# Blank.net
KiCad netlist of a schematic drawn in Altium Designer
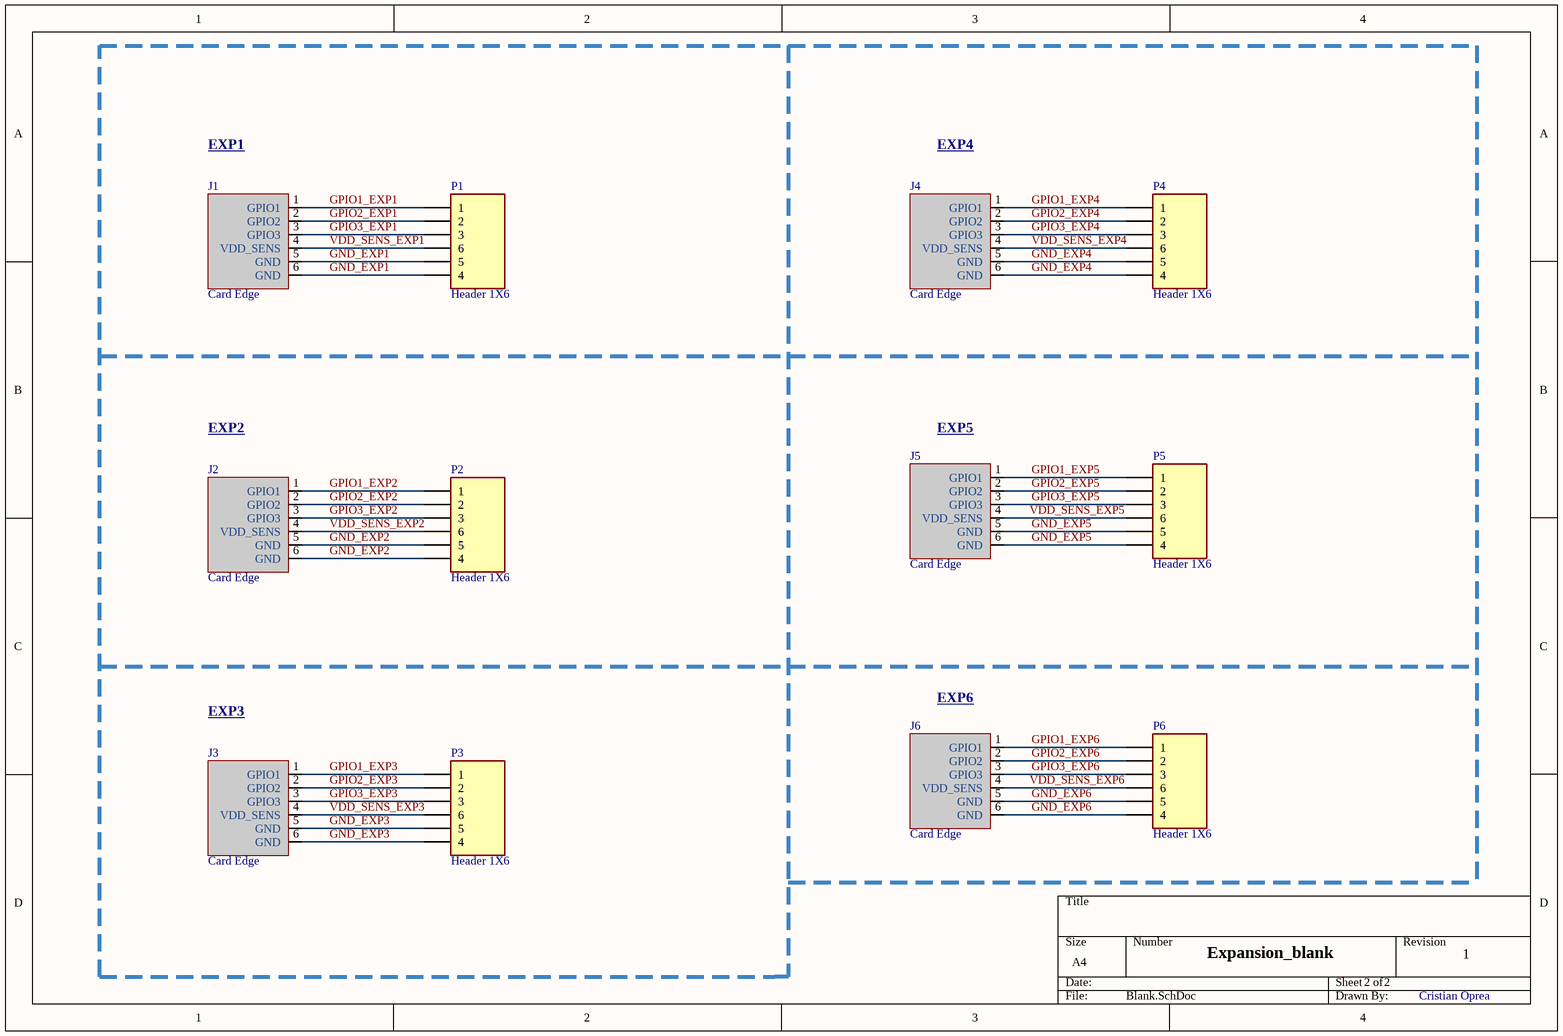
[diagram p0: Blank.SchDoc]

(export (version "E")
  (design (tool "Eeschema 10.0.6"))
  (components
    (comp (ref "J1")
      (value "Card Edge")
      (footprint "Card Edge")
      (description "Card Edge pads for 2.54 mm pitch edge connector")
      (libsource (lib "Schlib1") (part "Card Edge"))
    )
    (comp (ref "J2")
      (value "Card Edge")
      (footprint "Card Edge")
      (description "Card Edge pads for 2.54 mm pitch edge connector")
      (libsource (lib "Schlib1") (part "Card Edge"))
    )
    (comp (ref "J3")
      (value "Card Edge")
      (footprint "Card Edge")
      (description "Card Edge pads for 2.54 mm pitch edge connector")
      (libsource (lib "Schlib1") (part "Card Edge"))
    )
    (comp (ref "J4")
      (value "Card Edge")
      (footprint "Card Edge")
      (description "Card Edge pads for 2.54 mm pitch edge connector")
      (libsource (lib "Schlib1") (part "Card Edge"))
    )
    (comp (ref "J5")
      (value "Card Edge")
      (footprint "Card Edge")
      (description "Card Edge pads for 2.54 mm pitch edge connector")
      (libsource (lib "Schlib1") (part "Card Edge"))
    )
    (comp (ref "J6")
      (value "Card Edge")
      (footprint "Card Edge")
      (description "Card Edge pads for 2.54 mm pitch edge connector")
      (libsource (lib "Schlib1") (part "Card Edge"))
    )
    (comp (ref "P1")
      (value "Header 1X6")
      (footprint "HDR2X32")
      (description "Header,6-Pin, Single row")
      (fields (field (name "PUBLISHER") "Altium Limited"))
      (libsource (lib "Schlib1") (part "Header 1X6"))
    )
    (comp (ref "P2")
      (value "Header 1X6")
      (footprint "HDR2X32")
      (description "Header,6-Pin, Single row")
      (fields (field (name "PUBLISHER") "Altium Limited"))
      (libsource (lib "Schlib1") (part "Header 1X6"))
    )
    (comp (ref "P3")
      (value "Header 1X6")
      (footprint "HDR2X32")
      (description "Header,6-Pin, Single row")
      (fields (field (name "PUBLISHER") "Altium Limited"))
      (libsource (lib "Schlib1") (part "Header 1X6"))
    )
    (comp (ref "P4")
      (value "Header 1X6")
      (footprint "HDR2X32")
      (description "Header,6-Pin, Single row")
      (fields (field (name "PUBLISHER") "Altium Limited"))
      (libsource (lib "Schlib1") (part "Header 1X6"))
    )
    (comp (ref "P5")
      (value "Header 1X6")
      (footprint "HDR2X32")
      (description "Header,6-Pin, Single row")
      (fields (field (name "PUBLISHER") "Altium Limited"))
      (libsource (lib "Schlib1") (part "Header 1X6"))
    )
    (comp (ref "P6")
      (value "Header 1X6")
      (footprint "HDR2X32")
      (description "Header,6-Pin, Single row")
      (fields (field (name "PUBLISHER") "Altium Limited"))
      (libsource (lib "Schlib1") (part "Header 1X6"))
    )
  )
  (nets
    (net (code "1") (name "/GND_EXP1") (class "Default")
      (node (ref "J1") (pin "5") (pinfunction "GND_5") (pintype "passive"))
      (node (ref "J1") (pin "6") (pinfunction "GND_6") (pintype "passive"))
      (node (ref "P1") (pin "4") (pinfunction "4_4") (pintype "passive"))
      (node (ref "P1") (pin "5") (pinfunction "5_5") (pintype "passive"))
    )
    (net (code "2") (name "/GND_EXP2") (class "Default")
      (node (ref "J2") (pin "5") (pinfunction "GND_5") (pintype "passive"))
      (node (ref "J2") (pin "6") (pinfunction "GND_6") (pintype "passive"))
      (node (ref "P2") (pin "4") (pinfunction "4_4") (pintype "passive"))
      (node (ref "P2") (pin "5") (pinfunction "5_5") (pintype "passive"))
    )
    (net (code "3") (name "/GND_EXP3") (class "Default")
      (node (ref "J3") (pin "5") (pinfunction "GND_5") (pintype "passive"))
      (node (ref "J3") (pin "6") (pinfunction "GND_6") (pintype "passive"))
      (node (ref "P3") (pin "4") (pinfunction "4_4") (pintype "passive"))
      (node (ref "P3") (pin "5") (pinfunction "5_5") (pintype "passive"))
    )
    (net (code "4") (name "/GND_EXP4") (class "Default")
      (node (ref "J4") (pin "5") (pinfunction "GND_5") (pintype "passive"))
      (node (ref "J4") (pin "6") (pinfunction "GND_6") (pintype "passive"))
      (node (ref "P4") (pin "4") (pinfunction "4_4") (pintype "passive"))
      (node (ref "P4") (pin "5") (pinfunction "5_5") (pintype "passive"))
    )
    (net (code "5") (name "/GND_EXP5") (class "Default")
      (node (ref "J5") (pin "5") (pinfunction "GND_5") (pintype "passive"))
      (node (ref "J5") (pin "6") (pinfunction "GND_6") (pintype "passive"))
      (node (ref "P5") (pin "4") (pinfunction "4_4") (pintype "passive"))
      (node (ref "P5") (pin "5") (pinfunction "5_5") (pintype "passive"))
    )
    (net (code "6") (name "/GND_EXP6") (class "Default")
      (node (ref "J6") (pin "5") (pinfunction "GND_5") (pintype "passive"))
      (node (ref "J6") (pin "6") (pinfunction "GND_6") (pintype "passive"))
      (node (ref "P6") (pin "4") (pinfunction "4_4") (pintype "passive"))
      (node (ref "P6") (pin "5") (pinfunction "5_5") (pintype "passive"))
    )
    (net (code "7") (name "/GPIO1_EXP1") (class "Default")
      (node (ref "J1") (pin "1") (pinfunction "GPIO1_1") (pintype "passive"))
      (node (ref "P1") (pin "1") (pinfunction "1_1") (pintype "passive"))
    )
    (net (code "8") (name "/GPIO1_EXP2") (class "Default")
      (node (ref "J2") (pin "1") (pinfunction "GPIO1_1") (pintype "passive"))
      (node (ref "P2") (pin "1") (pinfunction "1_1") (pintype "passive"))
    )
    (net (code "9") (name "/GPIO1_EXP3") (class "Default")
      (node (ref "J3") (pin "1") (pinfunction "GPIO1_1") (pintype "passive"))
      (node (ref "P3") (pin "1") (pinfunction "1_1") (pintype "passive"))
    )
    (net (code "10") (name "/GPIO1_EXP4") (class "Default")
      (node (ref "J4") (pin "1") (pinfunction "GPIO1_1") (pintype "passive"))
      (node (ref "P4") (pin "1") (pinfunction "1_1") (pintype "passive"))
    )
    (net (code "11") (name "/GPIO1_EXP5") (class "Default")
      (node (ref "J5") (pin "1") (pinfunction "GPIO1_1") (pintype "passive"))
      (node (ref "P5") (pin "1") (pinfunction "1_1") (pintype "passive"))
    )
    (net (code "12") (name "/GPIO1_EXP6") (class "Default")
      (node (ref "J6") (pin "1") (pinfunction "GPIO1_1") (pintype "passive"))
      (node (ref "P6") (pin "1") (pinfunction "1_1") (pintype "passive"))
    )
    (net (code "13") (name "/GPIO2_EXP1") (class "Default")
      (node (ref "J1") (pin "2") (pinfunction "GPIO2_2") (pintype "passive"))
      (node (ref "P1") (pin "2") (pinfunction "2_2") (pintype "passive"))
    )
    (net (code "14") (name "/GPIO2_EXP2") (class "Default")
      (node (ref "J2") (pin "2") (pinfunction "GPIO2_2") (pintype "passive"))
      (node (ref "P2") (pin "2") (pinfunction "2_2") (pintype "passive"))
    )
    (net (code "15") (name "/GPIO2_EXP3") (class "Default")
      (node (ref "J3") (pin "2") (pinfunction "GPIO2_2") (pintype "passive"))
      (node (ref "P3") (pin "2") (pinfunction "2_2") (pintype "passive"))
    )
    (net (code "16") (name "/GPIO2_EXP4") (class "Default")
      (node (ref "J4") (pin "2") (pinfunction "GPIO2_2") (pintype "passive"))
      (node (ref "P4") (pin "2") (pinfunction "2_2") (pintype "passive"))
    )
    (net (code "17") (name "/GPIO2_EXP5") (class "Default")
      (node (ref "J5") (pin "2") (pinfunction "GPIO2_2") (pintype "passive"))
      (node (ref "P5") (pin "2") (pinfunction "2_2") (pintype "passive"))
    )
    (net (code "18") (name "/GPIO2_EXP6") (class "Default")
      (node (ref "J6") (pin "2") (pinfunction "GPIO2_2") (pintype "passive"))
      (node (ref "P6") (pin "2") (pinfunction "2_2") (pintype "passive"))
    )
    (net (code "19") (name "/GPIO3_EXP1") (class "Default")
      (node (ref "J1") (pin "3") (pinfunction "GPIO3_3") (pintype "passive"))
      (node (ref "P1") (pin "3") (pinfunction "3_3") (pintype "passive"))
    )
    (net (code "20") (name "/GPIO3_EXP2") (class "Default")
      (node (ref "J2") (pin "3") (pinfunction "GPIO3_3") (pintype "passive"))
      (node (ref "P2") (pin "3") (pinfunction "3_3") (pintype "passive"))
    )
    (net (code "21") (name "/GPIO3_EXP3") (class "Default")
      (node (ref "J3") (pin "3") (pinfunction "GPIO3_3") (pintype "passive"))
      (node (ref "P3") (pin "3") (pinfunction "3_3") (pintype "passive"))
    )
    (net (code "22") (name "/GPIO3_EXP4") (class "Default")
      (node (ref "J4") (pin "3") (pinfunction "GPIO3_3") (pintype "passive"))
      (node (ref "P4") (pin "3") (pinfunction "3_3") (pintype "passive"))
    )
    (net (code "23") (name "/GPIO3_EXP5") (class "Default")
      (node (ref "J5") (pin "3") (pinfunction "GPIO3_3") (pintype "passive"))
      (node (ref "P5") (pin "3") (pinfunction "3_3") (pintype "passive"))
    )
    (net (code "24") (name "/GPIO3_EXP6") (class "Default")
      (node (ref "J6") (pin "3") (pinfunction "GPIO3_3") (pintype "passive"))
      (node (ref "P6") (pin "3") (pinfunction "3_3") (pintype "passive"))
    )
    (net (code "25") (name "/VDD_SENS_EXP1") (class "Default")
      (node (ref "J1") (pin "4") (pinfunction "VDD_SENS_4") (pintype "passive"))
      (node (ref "P1") (pin "6") (pinfunction "6_6") (pintype "passive"))
    )
    (net (code "26") (name "/VDD_SENS_EXP2") (class "Default")
      (node (ref "J2") (pin "4") (pinfunction "VDD_SENS_4") (pintype "passive"))
      (node (ref "P2") (pin "6") (pinfunction "6_6") (pintype "passive"))
    )
    (net (code "27") (name "/VDD_SENS_EXP3") (class "Default")
      (node (ref "J3") (pin "4") (pinfunction "VDD_SENS_4") (pintype "passive"))
      (node (ref "P3") (pin "6") (pinfunction "6_6") (pintype "passive"))
    )
    (net (code "28") (name "/VDD_SENS_EXP4") (class "Default")
      (node (ref "J4") (pin "4") (pinfunction "VDD_SENS_4") (pintype "passive"))
      (node (ref "P4") (pin "6") (pinfunction "6_6") (pintype "passive"))
    )
    (net (code "29") (name "/VDD_SENS_EXP5") (class "Default")
      (node (ref "J5") (pin "4") (pinfunction "VDD_SENS_4") (pintype "passive"))
      (node (ref "P5") (pin "6") (pinfunction "6_6") (pintype "passive"))
    )
    (net (code "30") (name "/VDD_SENS_EXP6") (class "Default")
      (node (ref "J6") (pin "4") (pinfunction "VDD_SENS_4") (pintype "passive"))
      (node (ref "P6") (pin "6") (pinfunction "6_6") (pintype "passive"))
    )
  )
)
